# core.net
KiCad netlist of a schematic drawn in EAGLE
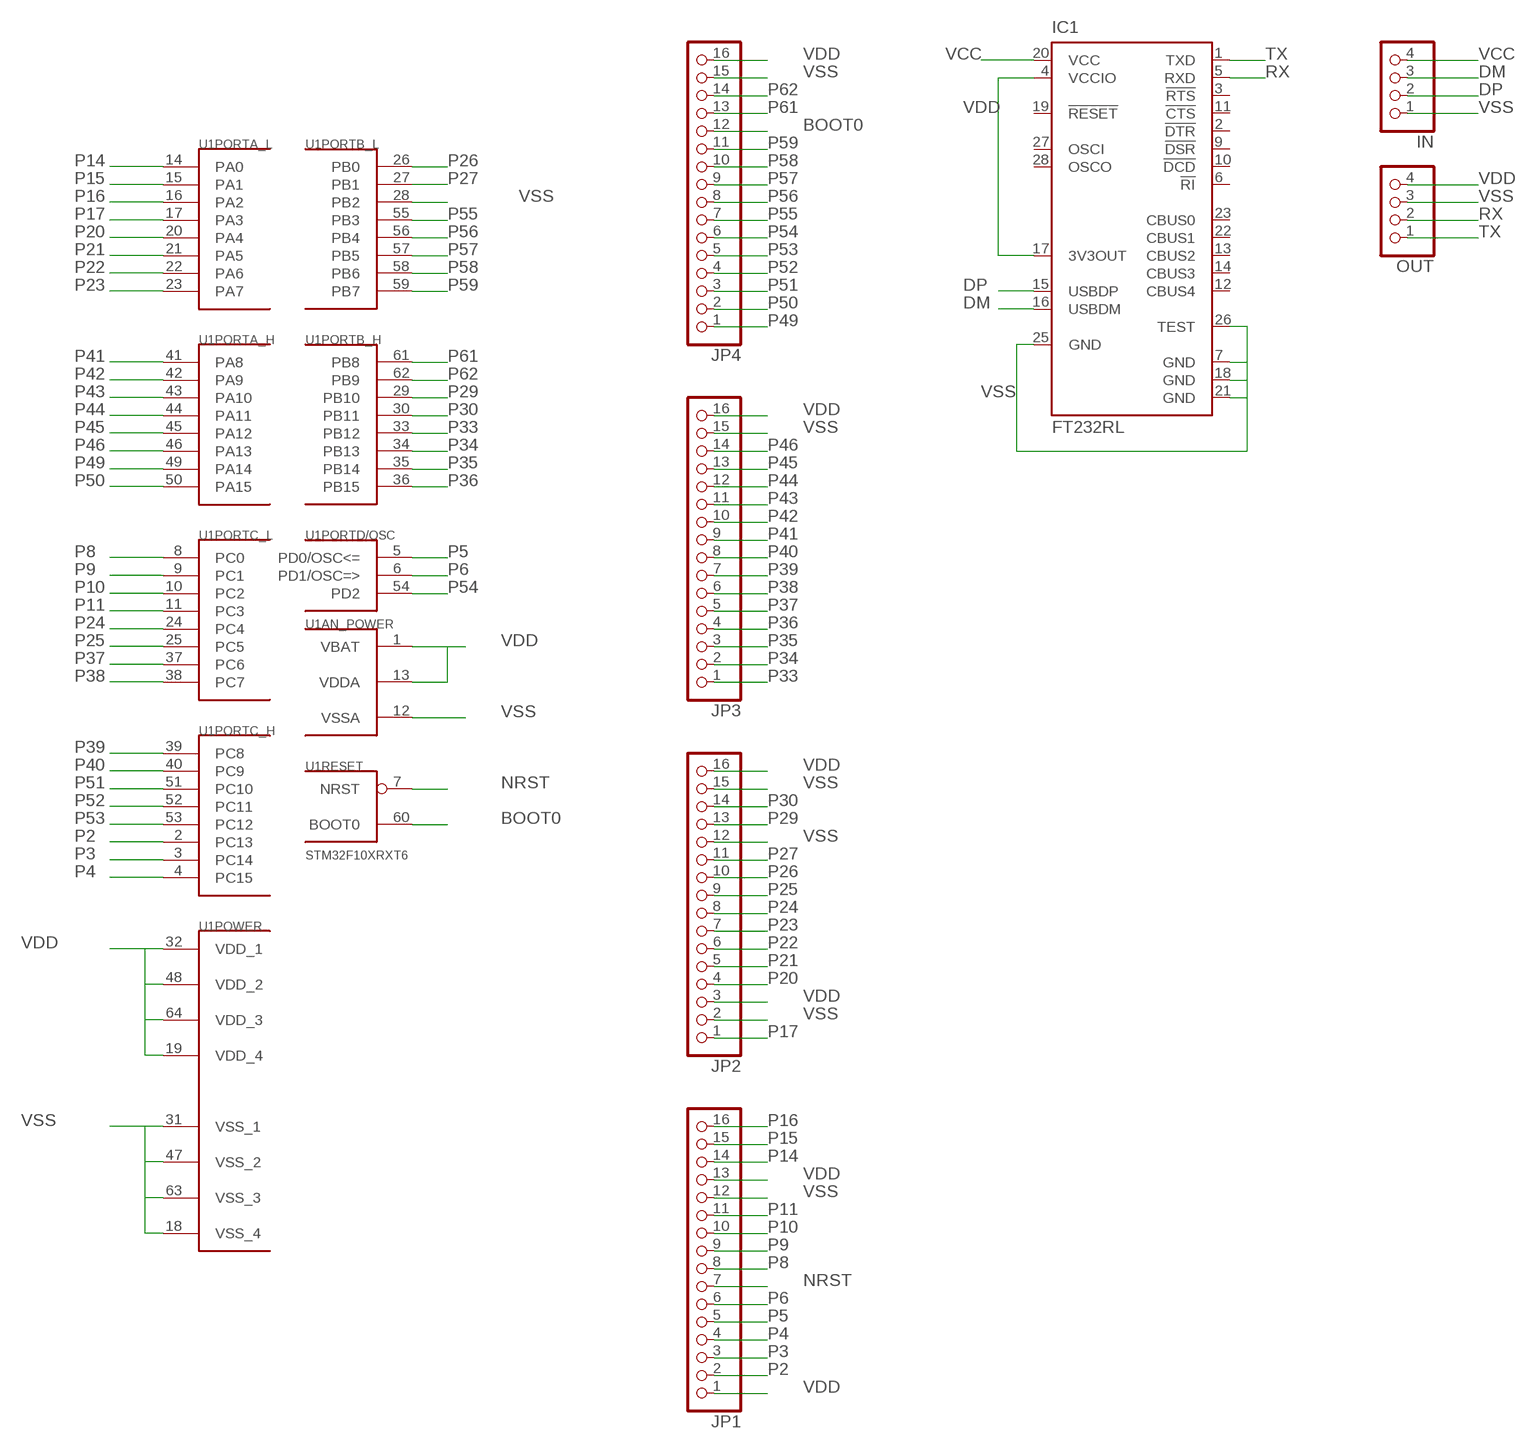
[diagram p0: schematic, sheet 1]

(export (version "E")
  (design (tool "Eeschema 10.0.6"))
  (components
    (comp (ref "IC1")
      (value "FT232RL")
      (footprint "eagle-import:SSOP28")
      (libsource (lib "eagle-import") (part "FT232RL"))
    )
    (comp (ref "IN")
      (value "PINHD-1X4")
      (footprint "eagle-import:1X04")
      (libsource (lib "eagle-import") (part "PINHD-1X4"))
    )
    (comp (ref "JP1")
      (value "PINHD-1X16")
      (footprint "eagle-import:1X16")
      (libsource (lib "eagle-import") (part "PINHD-1X16"))
    )
    (comp (ref "JP2")
      (value "PINHD-1X16")
      (footprint "eagle-import:1X16")
      (libsource (lib "eagle-import") (part "PINHD-1X16"))
    )
    (comp (ref "JP3")
      (value "PINHD-1X16")
      (footprint "eagle-import:1X16")
      (libsource (lib "eagle-import") (part "PINHD-1X16"))
    )
    (comp (ref "JP4")
      (value "PINHD-1X16")
      (footprint "eagle-import:1X16")
      (libsource (lib "eagle-import") (part "PINHD-1X16"))
    )
    (comp (ref "OUT")
      (value "PINHD-1X4")
      (footprint "eagle-import:1X04")
      (libsource (lib "eagle-import") (part "PINHD-1X4"))
    )
    (comp (ref "U1")
      (value "STM32F10XRXT6")
      (footprint "eagle-import:TQFP64")
      (libsource (lib "eagle-import") (part "STM32F10XRXT6"))
    )
  )
  (nets
    (net (code "1") (name "/BOOT0") (class "Default")
      (node (ref "JP4") (pin "12") (pinfunction "12_12") (pintype "passive"))
      (node (ref "U1") (pin "60") (pinfunction "BOOT0_60") (pintype "input"))
    )
    (net (code "2") (name "/DM") (class "Default")
      (node (ref "IC1") (pin "16") (pinfunction "USBDM_16") (pintype "bidirectional"))
      (node (ref "IN") (pin "3") (pinfunction "3_3") (pintype "passive"))
    )
    (net (code "3") (name "/DP") (class "Default")
      (node (ref "IC1") (pin "15") (pinfunction "USBDP_15") (pintype "bidirectional"))
      (node (ref "IN") (pin "2") (pinfunction "2_2") (pintype "passive"))
    )
    (net (code "4") (name "/NRST") (class "Default")
      (node (ref "JP1") (pin "7") (pinfunction "7_7") (pintype "passive"))
      (node (ref "U1") (pin "7") (pinfunction "NRST_7") (pintype "input"))
    )
    (net (code "5") (name "/P2") (class "Default")
      (node (ref "JP1") (pin "2") (pinfunction "2_2") (pintype "passive"))
      (node (ref "U1") (pin "2") (pinfunction "PC13_2") (pintype "bidirectional"))
    )
    (net (code "6") (name "/P3") (class "Default")
      (node (ref "JP1") (pin "3") (pinfunction "3_3") (pintype "passive"))
      (node (ref "U1") (pin "3") (pinfunction "PC14_3") (pintype "bidirectional"))
    )
    (net (code "7") (name "/P4") (class "Default")
      (node (ref "JP1") (pin "4") (pinfunction "4_4") (pintype "passive"))
      (node (ref "U1") (pin "4") (pinfunction "PC15_4") (pintype "bidirectional"))
    )
    (net (code "8") (name "/P5") (class "Default")
      (node (ref "JP1") (pin "5") (pinfunction "5_5") (pintype "passive"))
      (node (ref "U1") (pin "5") (pinfunction "PD0/OSC<=_5") (pintype "bidirectional"))
    )
    (net (code "9") (name "/P6") (class "Default")
      (node (ref "JP1") (pin "6") (pinfunction "6_6") (pintype "passive"))
      (node (ref "U1") (pin "6") (pinfunction "PD1/OSC=>_6") (pintype "bidirectional"))
    )
    (net (code "10") (name "/P8") (class "Default")
      (node (ref "JP1") (pin "8") (pinfunction "8_8") (pintype "passive"))
      (node (ref "U1") (pin "8") (pinfunction "PC0_8") (pintype "bidirectional"))
    )
    (net (code "11") (name "/P9") (class "Default")
      (node (ref "JP1") (pin "9") (pinfunction "9_9") (pintype "passive"))
      (node (ref "U1") (pin "9") (pinfunction "PC1_9") (pintype "bidirectional"))
    )
    (net (code "12") (name "/P10") (class "Default")
      (node (ref "JP1") (pin "10") (pinfunction "10_10") (pintype "passive"))
      (node (ref "U1") (pin "10") (pinfunction "PC2_10") (pintype "bidirectional"))
    )
    (net (code "13") (name "/P11") (class "Default")
      (node (ref "JP1") (pin "11") (pinfunction "11_11") (pintype "passive"))
      (node (ref "U1") (pin "11") (pinfunction "PC3_11") (pintype "bidirectional"))
    )
    (net (code "14") (name "/P14") (class "Default")
      (node (ref "JP1") (pin "14") (pinfunction "14_14") (pintype "passive"))
      (node (ref "U1") (pin "14") (pinfunction "PA0_14") (pintype "bidirectional"))
    )
    (net (code "15") (name "/P15") (class "Default")
      (node (ref "JP1") (pin "15") (pinfunction "15_15") (pintype "passive"))
      (node (ref "U1") (pin "15") (pinfunction "PA1_15") (pintype "bidirectional"))
    )
    (net (code "16") (name "/P16") (class "Default")
      (node (ref "JP1") (pin "16") (pinfunction "16_16") (pintype "passive"))
      (node (ref "U1") (pin "16") (pinfunction "PA2_16") (pintype "bidirectional"))
    )
    (net (code "17") (name "/P17") (class "Default")
      (node (ref "JP2") (pin "1") (pinfunction "1_1") (pintype "passive"))
      (node (ref "U1") (pin "17") (pinfunction "PA3_17") (pintype "bidirectional"))
    )
    (net (code "18") (name "/P20") (class "Default")
      (node (ref "JP2") (pin "4") (pinfunction "4_4") (pintype "passive"))
      (node (ref "U1") (pin "20") (pinfunction "PA4_20") (pintype "bidirectional"))
    )
    (net (code "19") (name "/P21") (class "Default")
      (node (ref "JP2") (pin "5") (pinfunction "5_5") (pintype "passive"))
      (node (ref "U1") (pin "21") (pinfunction "PA5_21") (pintype "bidirectional"))
    )
    (net (code "20") (name "/P22") (class "Default")
      (node (ref "JP2") (pin "6") (pinfunction "6_6") (pintype "passive"))
      (node (ref "U1") (pin "22") (pinfunction "PA6_22") (pintype "bidirectional"))
    )
    (net (code "21") (name "/P23") (class "Default")
      (node (ref "JP2") (pin "7") (pinfunction "7_7") (pintype "passive"))
      (node (ref "U1") (pin "23") (pinfunction "PA7_23") (pintype "bidirectional"))
    )
    (net (code "22") (name "/P24") (class "Default")
      (node (ref "JP2") (pin "8") (pinfunction "8_8") (pintype "passive"))
      (node (ref "U1") (pin "24") (pinfunction "PC4_24") (pintype "bidirectional"))
    )
    (net (code "23") (name "/P25") (class "Default")
      (node (ref "JP2") (pin "9") (pinfunction "9_9") (pintype "passive"))
      (node (ref "U1") (pin "25") (pinfunction "PC5_25") (pintype "bidirectional"))
    )
    (net (code "24") (name "/P26") (class "Default")
      (node (ref "JP2") (pin "10") (pinfunction "10_10") (pintype "passive"))
      (node (ref "U1") (pin "26") (pinfunction "PB0_26") (pintype "bidirectional"))
    )
    (net (code "25") (name "/P27") (class "Default")
      (node (ref "JP2") (pin "11") (pinfunction "11_11") (pintype "passive"))
      (node (ref "U1") (pin "27") (pinfunction "PB1_27") (pintype "bidirectional"))
    )
    (net (code "26") (name "/P29") (class "Default")
      (node (ref "JP2") (pin "13") (pinfunction "13_13") (pintype "passive"))
      (node (ref "U1") (pin "29") (pinfunction "PB10_29") (pintype "bidirectional"))
    )
    (net (code "27") (name "/P30") (class "Default")
      (node (ref "JP2") (pin "14") (pinfunction "14_14") (pintype "passive"))
      (node (ref "U1") (pin "30") (pinfunction "PB11_30") (pintype "bidirectional"))
    )
    (net (code "28") (name "/P33") (class "Default")
      (node (ref "JP3") (pin "1") (pinfunction "1_1") (pintype "passive"))
      (node (ref "U1") (pin "33") (pinfunction "PB12_33") (pintype "bidirectional"))
    )
    (net (code "29") (name "/P34") (class "Default")
      (node (ref "JP3") (pin "2") (pinfunction "2_2") (pintype "passive"))
      (node (ref "U1") (pin "34") (pinfunction "PB13_34") (pintype "bidirectional"))
    )
    (net (code "30") (name "/P35") (class "Default")
      (node (ref "JP3") (pin "3") (pinfunction "3_3") (pintype "passive"))
      (node (ref "U1") (pin "35") (pinfunction "PB14_35") (pintype "bidirectional"))
    )
    (net (code "31") (name "/P36") (class "Default")
      (node (ref "JP3") (pin "4") (pinfunction "4_4") (pintype "passive"))
      (node (ref "U1") (pin "36") (pinfunction "PB15_36") (pintype "bidirectional"))
    )
    (net (code "32") (name "/P37") (class "Default")
      (node (ref "JP3") (pin "5") (pinfunction "5_5") (pintype "passive"))
      (node (ref "U1") (pin "37") (pinfunction "PC6_37") (pintype "bidirectional"))
    )
    (net (code "33") (name "/P38") (class "Default")
      (node (ref "JP3") (pin "6") (pinfunction "6_6") (pintype "passive"))
      (node (ref "U1") (pin "38") (pinfunction "PC7_38") (pintype "bidirectional"))
    )
    (net (code "34") (name "/P39") (class "Default")
      (node (ref "JP3") (pin "7") (pinfunction "7_7") (pintype "passive"))
      (node (ref "U1") (pin "39") (pinfunction "PC8_39") (pintype "bidirectional"))
    )
    (net (code "35") (name "/P40") (class "Default")
      (node (ref "JP3") (pin "8") (pinfunction "8_8") (pintype "passive"))
      (node (ref "U1") (pin "40") (pinfunction "PC9_40") (pintype "bidirectional"))
    )
    (net (code "36") (name "/P41") (class "Default")
      (node (ref "JP3") (pin "9") (pinfunction "9_9") (pintype "passive"))
      (node (ref "U1") (pin "41") (pinfunction "PA8_41") (pintype "bidirectional"))
    )
    (net (code "37") (name "/P42") (class "Default")
      (node (ref "JP3") (pin "10") (pinfunction "10_10") (pintype "passive"))
      (node (ref "U1") (pin "42") (pinfunction "PA9_42") (pintype "bidirectional"))
    )
    (net (code "38") (name "/P43") (class "Default")
      (node (ref "JP3") (pin "11") (pinfunction "11_11") (pintype "passive"))
      (node (ref "U1") (pin "43") (pinfunction "PA10_43") (pintype "bidirectional"))
    )
    (net (code "39") (name "/P44") (class "Default")
      (node (ref "JP3") (pin "12") (pinfunction "12_12") (pintype "passive"))
      (node (ref "U1") (pin "44") (pinfunction "PA11_44") (pintype "bidirectional"))
    )
    (net (code "40") (name "/P45") (class "Default")
      (node (ref "JP3") (pin "13") (pinfunction "13_13") (pintype "passive"))
      (node (ref "U1") (pin "45") (pinfunction "PA12_45") (pintype "bidirectional"))
    )
    (net (code "41") (name "/P46") (class "Default")
      (node (ref "JP3") (pin "14") (pinfunction "14_14") (pintype "passive"))
      (node (ref "U1") (pin "46") (pinfunction "PA13_46") (pintype "bidirectional"))
    )
    (net (code "42") (name "/P49") (class "Default")
      (node (ref "JP4") (pin "1") (pinfunction "1_1") (pintype "passive"))
      (node (ref "U1") (pin "49") (pinfunction "PA14_49") (pintype "bidirectional"))
    )
    (net (code "43") (name "/P50") (class "Default")
      (node (ref "JP4") (pin "2") (pinfunction "2_2") (pintype "passive"))
      (node (ref "U1") (pin "50") (pinfunction "PA15_50") (pintype "bidirectional"))
    )
    (net (code "44") (name "/P51") (class "Default")
      (node (ref "JP4") (pin "3") (pinfunction "3_3") (pintype "passive"))
      (node (ref "U1") (pin "51") (pinfunction "PC10_51") (pintype "bidirectional"))
    )
    (net (code "45") (name "/P52") (class "Default")
      (node (ref "JP4") (pin "4") (pinfunction "4_4") (pintype "passive"))
      (node (ref "U1") (pin "52") (pinfunction "PC11_52") (pintype "bidirectional"))
    )
    (net (code "46") (name "/P53") (class "Default")
      (node (ref "JP4") (pin "5") (pinfunction "5_5") (pintype "passive"))
      (node (ref "U1") (pin "53") (pinfunction "PC12_53") (pintype "bidirectional"))
    )
    (net (code "47") (name "/P54") (class "Default")
      (node (ref "JP4") (pin "6") (pinfunction "6_6") (pintype "passive"))
      (node (ref "U1") (pin "54") (pinfunction "PD2_54") (pintype "bidirectional"))
    )
    (net (code "48") (name "/P55") (class "Default")
      (node (ref "JP4") (pin "7") (pinfunction "7_7") (pintype "passive"))
      (node (ref "U1") (pin "55") (pinfunction "PB3_55") (pintype "bidirectional"))
    )
    (net (code "49") (name "/P56") (class "Default")
      (node (ref "JP4") (pin "8") (pinfunction "8_8") (pintype "passive"))
      (node (ref "U1") (pin "56") (pinfunction "PB4_56") (pintype "bidirectional"))
    )
    (net (code "50") (name "/P57") (class "Default")
      (node (ref "JP4") (pin "9") (pinfunction "9_9") (pintype "passive"))
      (node (ref "U1") (pin "57") (pinfunction "PB5_57") (pintype "bidirectional"))
    )
    (net (code "51") (name "/P58") (class "Default")
      (node (ref "JP4") (pin "10") (pinfunction "10_10") (pintype "passive"))
      (node (ref "U1") (pin "58") (pinfunction "PB6_58") (pintype "bidirectional"))
    )
    (net (code "52") (name "/P59") (class "Default")
      (node (ref "JP4") (pin "11") (pinfunction "11_11") (pintype "passive"))
      (node (ref "U1") (pin "59") (pinfunction "PB7_59") (pintype "bidirectional"))
    )
    (net (code "53") (name "/P61") (class "Default")
      (node (ref "JP4") (pin "13") (pinfunction "13_13") (pintype "passive"))
      (node (ref "U1") (pin "61") (pinfunction "PB8_61") (pintype "bidirectional"))
    )
    (net (code "54") (name "/P62") (class "Default")
      (node (ref "JP4") (pin "14") (pinfunction "14_14") (pintype "passive"))
      (node (ref "U1") (pin "62") (pinfunction "PB9_62") (pintype "bidirectional"))
    )
    (net (code "55") (name "/RX") (class "Default")
      (node (ref "IC1") (pin "5") (pinfunction "RXD_5") (pintype "input"))
      (node (ref "OUT") (pin "2") (pinfunction "2_2") (pintype "passive"))
    )
    (net (code "56") (name "/TX") (class "Default")
      (node (ref "IC1") (pin "1") (pinfunction "TXD_1") (pintype "output"))
      (node (ref "OUT") (pin "1") (pinfunction "1_1") (pintype "passive"))
    )
    (net (code "57") (name "/VCC") (class "Default")
      (node (ref "IC1") (pin "20") (pinfunction "VCC_20") (pintype "power_in"))
      (node (ref "IN") (pin "4") (pinfunction "4_4") (pintype "passive"))
    )
    (net (code "58") (name "/VDD") (class "Default")
      (node (ref "IC1") (pin "17") (pinfunction "3V3OUT_17") (pintype "output"))
      (node (ref "IC1") (pin "4") (pinfunction "VCCIO_4") (pintype "power_in"))
      (node (ref "JP1") (pin "1") (pinfunction "1_1") (pintype "passive"))
      (node (ref "JP1") (pin "13") (pinfunction "13_13") (pintype "passive"))
      (node (ref "JP2") (pin "16") (pinfunction "16_16") (pintype "passive"))
      (node (ref "JP2") (pin "3") (pinfunction "3_3") (pintype "passive"))
      (node (ref "JP3") (pin "16") (pinfunction "16_16") (pintype "passive"))
      (node (ref "JP4") (pin "16") (pinfunction "16_16") (pintype "passive"))
      (node (ref "OUT") (pin "4") (pinfunction "4_4") (pintype "passive"))
      (node (ref "U1") (pin "1") (pinfunction "VBAT_1") (pintype "power_in"))
      (node (ref "U1") (pin "13") (pinfunction "VDDA_13") (pintype "power_in"))
      (node (ref "U1") (pin "19") (pinfunction "VDD_4_19") (pintype "power_in"))
      (node (ref "U1") (pin "32") (pinfunction "VDD_1_32") (pintype "power_in"))
      (node (ref "U1") (pin "48") (pinfunction "VDD_2_48") (pintype "power_in"))
      (node (ref "U1") (pin "64") (pinfunction "VDD_3_64") (pintype "power_in"))
    )
    (net (code "59") (name "/VSS") (class "Default")
      (node (ref "IC1") (pin "18") (pinfunction "GND_18") (pintype "power_in"))
      (node (ref "IC1") (pin "21") (pinfunction "GND_21") (pintype "power_in"))
      (node (ref "IC1") (pin "25") (pinfunction "GND_25") (pintype "power_in"))
      (node (ref "IC1") (pin "26") (pinfunction "TEST_26") (pintype "input"))
      (node (ref "IC1") (pin "7") (pinfunction "GND_7") (pintype "power_in"))
      (node (ref "IN") (pin "1") (pinfunction "1_1") (pintype "passive"))
      (node (ref "JP1") (pin "12") (pinfunction "12_12") (pintype "passive"))
      (node (ref "JP2") (pin "12") (pinfunction "12_12") (pintype "passive"))
      (node (ref "JP2") (pin "15") (pinfunction "15_15") (pintype "passive"))
      (node (ref "JP2") (pin "2") (pinfunction "2_2") (pintype "passive"))
      (node (ref "JP3") (pin "15") (pinfunction "15_15") (pintype "passive"))
      (node (ref "JP4") (pin "15") (pinfunction "15_15") (pintype "passive"))
      (node (ref "OUT") (pin "3") (pinfunction "3_3") (pintype "passive"))
      (node (ref "U1") (pin "12") (pinfunction "VSSA_12") (pintype "power_in"))
      (node (ref "U1") (pin "18") (pinfunction "VSS_4_18") (pintype "power_in"))
      (node (ref "U1") (pin "28") (pinfunction "PB2_28") (pintype "bidirectional"))
      (node (ref "U1") (pin "31") (pinfunction "VSS_1_31") (pintype "power_in"))
      (node (ref "U1") (pin "47") (pinfunction "VSS_2_47") (pintype "power_in"))
      (node (ref "U1") (pin "63") (pinfunction "VSS_3_63") (pintype "power_in"))
    )
    (net (code "60") (name "unconnected-(IC1-CBUS0-Pad23)") (class "Default")
      (node (ref "IC1") (pin "23") (pinfunction "CBUS0_23") (pintype "bidirectional"))
    )
    (net (code "61") (name "unconnected-(IC1-CBUS1-Pad22)") (class "Default")
      (node (ref "IC1") (pin "22") (pinfunction "CBUS1_22") (pintype "bidirectional"))
    )
    (net (code "62") (name "unconnected-(IC1-CBUS2-Pad13)") (class "Default")
      (node (ref "IC1") (pin "13") (pinfunction "CBUS2_13") (pintype "bidirectional"))
    )
    (net (code "63") (name "unconnected-(IC1-CBUS3-Pad14)") (class "Default")
      (node (ref "IC1") (pin "14") (pinfunction "CBUS3_14") (pintype "bidirectional"))
    )
    (net (code "64") (name "unconnected-(IC1-CBUS4-Pad12)") (class "Default")
      (node (ref "IC1") (pin "12") (pinfunction "CBUS4_12") (pintype "bidirectional"))
    )
    (net (code "65") (name "unconnected-(IC1-OSCI-Pad27)") (class "Default")
      (node (ref "IC1") (pin "27") (pinfunction "OSCI_27") (pintype "input"))
    )
    (net (code "66") (name "unconnected-(IC1-OSCO-Pad28)") (class "Default")
      (node (ref "IC1") (pin "28") (pinfunction "OSCO_28") (pintype "output"))
    )
    (net (code "67") (name "unconnected-(IC1-~{CTS}-Pad11)") (class "Default")
      (node (ref "IC1") (pin "11") (pinfunction "~{CTS}_11") (pintype "input"))
    )
    (net (code "68") (name "unconnected-(IC1-~{DCD}-Pad10)") (class "Default")
      (node (ref "IC1") (pin "10") (pinfunction "~{DCD}_10") (pintype "input"))
    )
    (net (code "69") (name "unconnected-(IC1-~{DSR}-Pad9)") (class "Default")
      (node (ref "IC1") (pin "9") (pinfunction "~{DSR}_9") (pintype "input"))
    )
    (net (code "70") (name "unconnected-(IC1-~{DTR}-Pad2)") (class "Default")
      (node (ref "IC1") (pin "2") (pinfunction "~{DTR}_2") (pintype "output"))
    )
    (net (code "71") (name "unconnected-(IC1-~{RESET}-Pad19)") (class "Default")
      (node (ref "IC1") (pin "19") (pinfunction "~{RESET}_19") (pintype "input"))
    )
    (net (code "72") (name "unconnected-(IC1-~{RI}-Pad6)") (class "Default")
      (node (ref "IC1") (pin "6") (pinfunction "~{RI}_6") (pintype "input"))
    )
    (net (code "73") (name "unconnected-(IC1-~{RTS}-Pad3)") (class "Default")
      (node (ref "IC1") (pin "3") (pinfunction "~{RTS}_3") (pintype "output"))
    )
  )
)
